# OMAPL-137-Manchester.net
KiCad netlist of a schematic drawn in Altium Designer
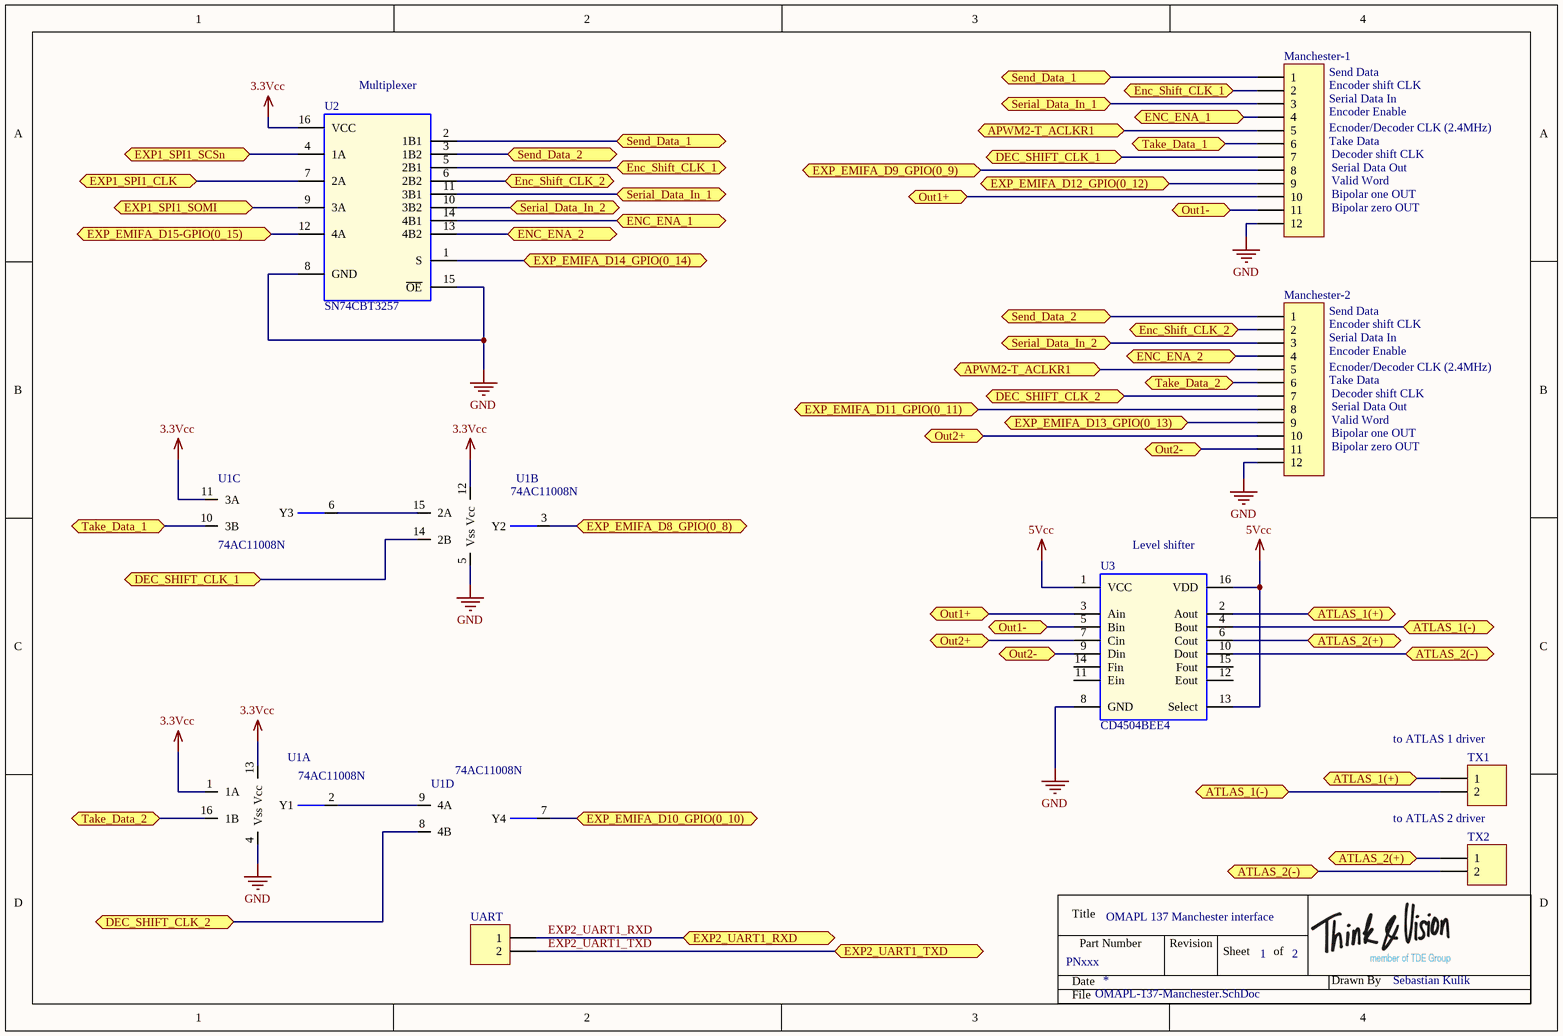
[diagram p0: OMAPL-137-Manchester.SchDoc]

(export (version "E")
  (design (tool "Eeschema 10.0.6"))
  (components
    (comp (ref "Manchester-1")
      (value "Plug_12_2.54")
      (footprint "HDR1X12_2.54")
      (description "Plug, 11-Pin")
      (fields (field (name "MANUFACTURER") "WE") (field (name "PUBLISHER") "Sebastian Kulik"))
      (libsource (lib "Connectors") (part "Plug_12_2.54"))
    )
    (comp (ref "Manchester-2")
      (value "Plug_12_2.54")
      (footprint "HDR1X12_2.54")
      (description "Plug, 11-Pin")
      (fields (field (name "MANUFACTURER") "WE") (field (name "PUBLISHER") "Sebastian Kulik"))
      (libsource (lib "Connectors") (part "Plug_12_2.54"))
    )
    (comp (ref "TX1")
      (value "Plug_2_90_2.54")
      (footprint "HDR1X2")
      (description "Plug, 2-Pin")
      (fields (field (name "MANUFACTURER") "WE") (field (name "PUBLISHER") "Sebastian Kulik"))
      (libsource (lib "Connectors") (part "Plug_2_90_2.54"))
    )
    (comp (ref "TX2")
      (value "Plug_2_90_2.54")
      (footprint "HDR1X2")
      (description "Plug, 2-Pin")
      (fields (field (name "MANUFACTURER") "WE") (field (name "PUBLISHER") "Sebastian Kulik"))
      (libsource (lib "Connectors") (part "Plug_2_90_2.54"))
    )
    (comp (ref "U1")
      (value "74AC11008N")
      (footprint "SO-16_L")
      (description "Quad AND, TTL")
      (fields (field (name "MANUFACTURER") "TI") (field (name "PUBLISHER") "Sebastian Kulik"))
      (libsource (lib "ICs") (part "74AC11008N"))
    )
    (comp (ref "U2")
      (value "SN74CBT3257")
      (footprint "SOIC16_N")
      (description "LV 4BIT FET MUX/DEMUX")
      (fields (field (name "MANUFACTURER") "TI") (field (name "PUBLISHER") "Sebastian Kulik"))
      (libsource (lib "ICs") (part "SN74CBT3257"))
    )
    (comp (ref "U3")
      (value "CD4504BEE4")
      (footprint "DIP-16")
      (description "20V Level shifter")
      (fields (field (name "MANUFACTURER") "TI") (field (name "PUBLISHER") "Sebastian Kulik"))
      (libsource (lib "ICs") (part "CD4504BEE4"))
    )
    (comp (ref "UART")
      (value "Plug_2_90_2.54")
      (footprint "HDR1X2")
      (description "Plug, 2-Pin")
      (fields (field (name "MANUFACTURER") "WE") (field (name "PUBLISHER") "Sebastian Kulik"))
      (libsource (lib "") (part "Plug_2_90_2.54_1"))
    )
  )
  (nets
    (net (code "1") (name "/APWM2-T_ACLKR1") (class "Default")
      (node (ref "Manchester-1") (pin "5") (pinfunction "5_5") (pintype "passive"))
      (node (ref "Manchester-2") (pin "5") (pinfunction "5_5") (pintype "passive"))
    )
    (net (code "2") (name "/ATLAS_1(+)") (class "Default")
      (node (ref "TX1") (pin "1") (pinfunction "1_1") (pintype "passive"))
      (node (ref "U3") (pin "2") (pinfunction "Aout_2") (pintype "passive"))
    )
    (net (code "3") (name "/ATLAS_1(-)") (class "Default")
      (node (ref "TX1") (pin "2") (pinfunction "2_2") (pintype "passive"))
      (node (ref "U3") (pin "4") (pinfunction "Bout_4") (pintype "passive"))
    )
    (net (code "4") (name "/ATLAS_2(+)") (class "Default")
      (node (ref "TX2") (pin "1") (pinfunction "1_1") (pintype "passive"))
      (node (ref "U3") (pin "6") (pinfunction "Cout_6") (pintype "passive"))
    )
    (net (code "5") (name "/ATLAS_2(-)") (class "Default")
      (node (ref "TX2") (pin "2") (pinfunction "2_2") (pintype "passive"))
      (node (ref "U3") (pin "10") (pinfunction "Dout_10") (pintype "passive"))
    )
    (net (code "6") (name "/DEC_SHIFT_CLK_1") (class "Default")
      (node (ref "Manchester-1") (pin "7") (pinfunction "7_7") (pintype "passive"))
      (node (ref "U1") (pin "14") (pinfunction "2B_14") (pintype "passive"))
    )
    (net (code "7") (name "/DEC_SHIFT_CLK_2") (class "Default")
      (node (ref "Manchester-2") (pin "7") (pinfunction "7_7") (pintype "passive"))
      (node (ref "U1") (pin "8") (pinfunction "4B_8") (pintype "passive"))
    )
    (net (code "8") (name "/ENC_ENA_1") (class "Default")
      (node (ref "Manchester-1") (pin "4") (pinfunction "4_4") (pintype "passive"))
      (node (ref "U2") (pin "14") (pinfunction "4B1_14") (pintype "passive"))
    )
    (net (code "9") (name "/ENC_ENA_2") (class "Default")
      (node (ref "Manchester-2") (pin "4") (pinfunction "4_4") (pintype "passive"))
      (node (ref "U2") (pin "13") (pinfunction "4B2_13") (pintype "passive"))
    )
    (net (code "10") (name "/EXP1_SPI1_CLK") (class "Default")
      (node (ref "U2") (pin "7") (pinfunction "2A_7") (pintype "passive"))
    )
    (net (code "11") (name "/EXP1_SPI1_SCSn") (class "Default")
      (node (ref "U2") (pin "4") (pinfunction "1A_4") (pintype "passive"))
    )
    (net (code "12") (name "/EXP1_SPI1_SOMI") (class "Default")
      (node (ref "U2") (pin "9") (pinfunction "3A_9") (pintype "passive"))
    )
    (net (code "13") (name "/EXP2_UART1_RXD") (class "Default")
      (node (ref "UART") (pin "1") (pinfunction "1_1") (pintype "passive"))
    )
    (net (code "14") (name "/EXP2_UART1_TXD") (class "Default")
      (node (ref "UART") (pin "2") (pinfunction "2_2") (pintype "passive"))
    )
    (net (code "15") (name "/EXP_EMIFA_D8_GPIO(0_8)") (class "Default")
      (node (ref "U1") (pin "3") (pinfunction "Y2_3") (pintype "passive"))
    )
    (net (code "16") (name "/EXP_EMIFA_D9_GPIO(0_9)") (class "Default")
      (node (ref "Manchester-1") (pin "8") (pinfunction "8_8") (pintype "passive"))
    )
    (net (code "17") (name "/EXP_EMIFA_D10_GPIO(0_10)") (class "Default")
      (node (ref "U1") (pin "7") (pinfunction "Y4_7") (pintype "passive"))
    )
    (net (code "18") (name "/EXP_EMIFA_D11_GPIO(0_11)") (class "Default")
      (node (ref "Manchester-2") (pin "8") (pinfunction "8_8") (pintype "passive"))
    )
    (net (code "19") (name "/EXP_EMIFA_D12_GPIO(0_12)") (class "Default")
      (node (ref "Manchester-1") (pin "9") (pinfunction "9_9") (pintype "passive"))
    )
    (net (code "20") (name "/EXP_EMIFA_D13_GPIO(0_13)") (class "Default")
      (node (ref "Manchester-2") (pin "9") (pinfunction "9_9") (pintype "passive"))
    )
    (net (code "21") (name "/EXP_EMIFA_D14_GPIO(0_14)") (class "Default")
      (node (ref "U2") (pin "1") (pinfunction "S_1") (pintype "passive"))
    )
    (net (code "22") (name "/EXP_EMIFA_D15-GPIO(0_15)") (class "Default")
      (node (ref "U2") (pin "12") (pinfunction "4A_12") (pintype "passive"))
    )
    (net (code "23") (name "/Enc_Shift_CLK_1") (class "Default")
      (node (ref "Manchester-1") (pin "2") (pinfunction "2_2") (pintype "passive"))
      (node (ref "U2") (pin "5") (pinfunction "2B1_5") (pintype "passive"))
    )
    (net (code "24") (name "/Enc_Shift_CLK_2") (class "Default")
      (node (ref "Manchester-2") (pin "2") (pinfunction "2_2") (pintype "passive"))
      (node (ref "U2") (pin "6") (pinfunction "2B2_6") (pintype "passive"))
    )
    (net (code "25") (name "/Out1+") (class "Default")
      (node (ref "Manchester-1") (pin "10") (pinfunction "10_10") (pintype "passive"))
      (node (ref "U3") (pin "3") (pinfunction "Ain_3") (pintype "passive"))
    )
    (net (code "26") (name "/Out1-") (class "Default")
      (node (ref "Manchester-1") (pin "11") (pinfunction "11_11") (pintype "passive"))
      (node (ref "U3") (pin "5") (pinfunction "Bin_5") (pintype "passive"))
    )
    (net (code "27") (name "/Out2+") (class "Default")
      (node (ref "Manchester-2") (pin "10") (pinfunction "10_10") (pintype "passive"))
      (node (ref "U3") (pin "7") (pinfunction "Cin_7") (pintype "passive"))
    )
    (net (code "28") (name "/Out2-") (class "Default")
      (node (ref "Manchester-2") (pin "11") (pinfunction "11_11") (pintype "passive"))
      (node (ref "U3") (pin "9") (pinfunction "Din_9") (pintype "passive"))
    )
    (net (code "29") (name "/Send_Data_1") (class "Default")
      (node (ref "Manchester-1") (pin "1") (pinfunction "1_1") (pintype "passive"))
      (node (ref "U2") (pin "2") (pinfunction "1B1_2") (pintype "passive"))
    )
    (net (code "30") (name "/Send_Data_2") (class "Default")
      (node (ref "Manchester-2") (pin "1") (pinfunction "1_1") (pintype "passive"))
      (node (ref "U2") (pin "3") (pinfunction "1B2_3") (pintype "passive"))
    )
    (net (code "31") (name "/Serial_Data_In_1") (class "Default")
      (node (ref "Manchester-1") (pin "3") (pinfunction "3_3") (pintype "passive"))
      (node (ref "U2") (pin "11") (pinfunction "3B1_11") (pintype "passive"))
    )
    (net (code "32") (name "/Serial_Data_In_2") (class "Default")
      (node (ref "Manchester-2") (pin "3") (pinfunction "3_3") (pintype "passive"))
      (node (ref "U2") (pin "10") (pinfunction "3B2_10") (pintype "passive"))
    )
    (net (code "33") (name "/Take_Data_1") (class "Default")
      (node (ref "Manchester-1") (pin "6") (pinfunction "6_6") (pintype "passive"))
      (node (ref "U1") (pin "10") (pinfunction "3B_10") (pintype "passive"))
    )
    (net (code "34") (name "/Take_Data_2") (class "Default")
      (node (ref "Manchester-2") (pin "6") (pinfunction "6_6") (pintype "passive"))
      (node (ref "U1") (pin "16") (pinfunction "1B_16") (pintype "passive"))
    )
    (net (code "35") (name "3.3Vcc") (class "Default")
      (node (ref "U1") (pin "1") (pinfunction "1A_1") (pintype "passive"))
      (node (ref "U1") (pin "11") (pinfunction "3A_11") (pintype "passive"))
      (node (ref "U1") (pin "12") (pinfunction "Vcc_12") (pintype "passive"))
      (node (ref "U1") (pin "13") (pinfunction "Vcc_13") (pintype "passive"))
      (node (ref "U2") (pin "16") (pinfunction "VCC_16") (pintype "passive"))
    )
    (net (code "36") (name "5Vcc") (class "Default")
      (node (ref "U3") (pin "1") (pinfunction "VCC_1") (pintype "passive"))
      (node (ref "U3") (pin "13") (pinfunction "Select_13") (pintype "passive"))
      (node (ref "U3") (pin "16") (pinfunction "VDD_16") (pintype "passive"))
    )
    (net (code "37") (name "GND") (class "Default")
      (node (ref "Manchester-1") (pin "12") (pinfunction "12_12") (pintype "passive"))
      (node (ref "Manchester-2") (pin "12") (pinfunction "12_12") (pintype "passive"))
      (node (ref "U1") (pin "4") (pinfunction "Vss_4") (pintype "passive"))
      (node (ref "U1") (pin "5") (pinfunction "Vss_5") (pintype "passive"))
      (node (ref "U2") (pin "15") (pinfunction "~{OE}_15") (pintype "passive"))
      (node (ref "U2") (pin "8") (pinfunction "GND_8") (pintype "passive"))
      (node (ref "U3") (pin "8") (pinfunction "GND_8") (pintype "passive"))
    )
    (net (code "38") (name "Net-(U1A-Y1)") (class "Default")
      (node (ref "U1") (pin "2") (pinfunction "Y1_2") (pintype "passive"))
      (node (ref "U1") (pin "9") (pinfunction "4A_9") (pintype "passive"))
    )
    (net (code "39") (name "Net-(U1B-2A)") (class "Default")
      (node (ref "U1") (pin "15") (pinfunction "2A_15") (pintype "passive"))
      (node (ref "U1") (pin "6") (pinfunction "Y3_6") (pintype "passive"))
    )
    (net (code "40") (name "unconnected-(U3-Ein-Pad11)") (class "Default")
      (node (ref "U3") (pin "11") (pinfunction "Ein_11") (pintype "passive"))
    )
    (net (code "41") (name "unconnected-(U3-Eout-Pad12)") (class "Default")
      (node (ref "U3") (pin "12") (pinfunction "Eout_12") (pintype "passive"))
    )
    (net (code "42") (name "unconnected-(U3-Fin-Pad14)") (class "Default")
      (node (ref "U3") (pin "14") (pinfunction "Fin_14") (pintype "passive"))
    )
    (net (code "43") (name "unconnected-(U3-Fout-Pad15)") (class "Default")
      (node (ref "U3") (pin "15") (pinfunction "Fout_15") (pintype "passive"))
    )
  )
)
